# ArduinoV01.net
KiCad netlist of a schematic drawn in EAGLE
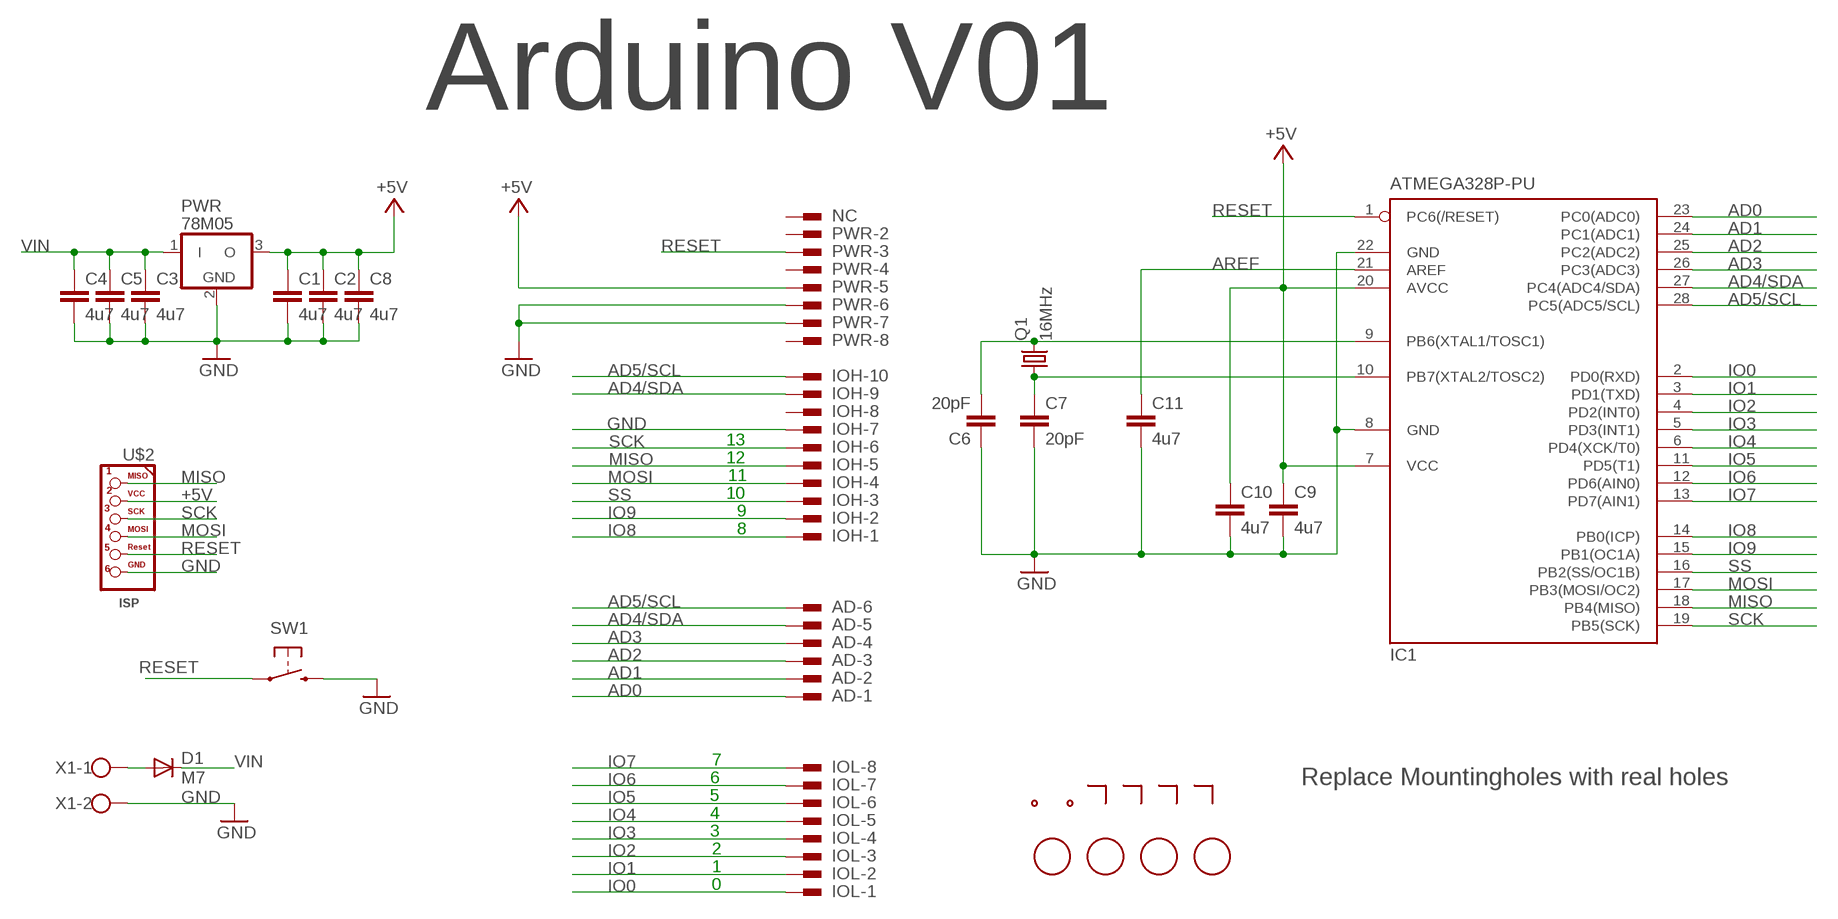
[diagram p0: schematic, sheet 1]

(export (version "E")
  (design (tool "Eeschema 10.0.6"))
  (components
    (comp (ref "AD-1")
      (value "PINHD-1X1")
      (footprint "eagle-import:1X01")
      (fields (field (name "MF") "TYCO ELECTRONICS") (field (name "MPN") "62221-1"))
      (libsource (lib "eagle-import") (part "PINHD-1X1"))
    )
    (comp (ref "AD-2")
      (value "PINHD-1X1")
      (footprint "eagle-import:1X01")
      (fields (field (name "MF") "TYCO ELECTRONICS") (field (name "MPN") "62221-1"))
      (libsource (lib "eagle-import") (part "PINHD-1X1"))
    )
    (comp (ref "AD-3")
      (value "PINHD-1X1")
      (footprint "eagle-import:1X01")
      (fields (field (name "MF") "TYCO ELECTRONICS") (field (name "MPN") "62221-1"))
      (libsource (lib "eagle-import") (part "PINHD-1X1"))
    )
    (comp (ref "AD-4")
      (value "PINHD-1X1")
      (footprint "eagle-import:1X01")
      (fields (field (name "MF") "TYCO ELECTRONICS") (field (name "MPN") "62221-1"))
      (libsource (lib "eagle-import") (part "PINHD-1X1"))
    )
    (comp (ref "AD-5")
      (value "PINHD-1X1")
      (footprint "eagle-import:1X01")
      (fields (field (name "MF") "TYCO ELECTRONICS") (field (name "MPN") "62221-1"))
      (libsource (lib "eagle-import") (part "PINHD-1X1"))
    )
    (comp (ref "AD-6")
      (value "PINHD-1X1")
      (footprint "eagle-import:1X01")
      (fields (field (name "MF") "TYCO ELECTRONICS") (field (name "MPN") "62221-1"))
      (libsource (lib "eagle-import") (part "PINHD-1X1"))
    )
    (comp (ref "C1")
      (value "4u7")
      (footprint "eagle-import:C0805")
      (libsource (lib "eagle-import") (part "C-EUC0805"))
    )
    (comp (ref "C2")
      (value "4u7")
      (footprint "eagle-import:C0805")
      (libsource (lib "eagle-import") (part "C-EUC0805"))
    )
    (comp (ref "C3")
      (value "4u7")
      (footprint "eagle-import:C0805")
      (libsource (lib "eagle-import") (part "C-EUC0805"))
    )
    (comp (ref "C4")
      (value "4u7")
      (footprint "eagle-import:C0805")
      (libsource (lib "eagle-import") (part "C-EUC0805"))
    )
    (comp (ref "C5")
      (value "4u7")
      (footprint "eagle-import:C0805")
      (libsource (lib "eagle-import") (part "C-EUC0805"))
    )
    (comp (ref "C6")
      (value "20pF")
      (footprint "eagle-import:C0805")
      (libsource (lib "eagle-import") (part "C-EUC0805"))
    )
    (comp (ref "C7")
      (value "20pF")
      (footprint "eagle-import:C0805")
      (libsource (lib "eagle-import") (part "C-EUC0805"))
    )
    (comp (ref "C8")
      (value "4u7")
      (footprint "eagle-import:C0805")
      (libsource (lib "eagle-import") (part "C-EUC0805"))
    )
    (comp (ref "C9")
      (value "4u7")
      (footprint "eagle-import:C0805")
      (libsource (lib "eagle-import") (part "C-EUC0805"))
    )
    (comp (ref "C10")
      (value "4u7")
      (footprint "eagle-import:C0805")
      (libsource (lib "eagle-import") (part "C-EUC0805"))
    )
    (comp (ref "C11")
      (value "4u7")
      (footprint "eagle-import:C0805")
      (libsource (lib "eagle-import") (part "C-EUC0805"))
    )
    (comp (ref "D1")
      (value "M7")
      (footprint "eagle-import:DO214AC")
      (libsource (lib "eagle-import") (part "DIODE-DO214AC"))
    )
    (comp (ref "FD1")
      (value "FIDUCIALMOUNT")
      (footprint "eagle-import:FIDUCIA-MOUNT")
      (libsource (lib "eagle-import") (part "FIDUCIALMOUNT"))
    )
    (comp (ref "FD2")
      (value "FIDUCIALMOUNT")
      (footprint "eagle-import:FIDUCIA-MOUNT")
      (libsource (lib "eagle-import") (part "FIDUCIALMOUNT"))
    )
    (comp (ref "FD3")
      (value "FIDUCIALMOUNT")
      (footprint "eagle-import:FIDUCIA-MOUNT")
      (libsource (lib "eagle-import") (part "FIDUCIALMOUNT"))
    )
    (comp (ref "FD4")
      (value "FIDUCIALMOUNT")
      (footprint "eagle-import:FIDUCIA-MOUNT")
      (libsource (lib "eagle-import") (part "FIDUCIALMOUNT"))
    )
    (comp (ref "IC1")
      (value "ATMEGA328P-PU")
      (footprint "eagle-import:DIL28-3")
      (libsource (lib "eagle-import") (part "ATMEGA328P-PU"))
    )
    (comp (ref "IOH-1")
      (value "PINHD-1X1")
      (footprint "eagle-import:1X01")
      (fields (field (name "MF") "TYCO ELECTRONICS") (field (name "MPN") "62221-1"))
      (libsource (lib "eagle-import") (part "PINHD-1X1"))
    )
    (comp (ref "IOH-2")
      (value "PINHD-1X1")
      (footprint "eagle-import:1X01")
      (fields (field (name "MF") "TYCO ELECTRONICS") (field (name "MPN") "62221-1"))
      (libsource (lib "eagle-import") (part "PINHD-1X1"))
    )
    (comp (ref "IOH-3")
      (value "PINHD-1X1")
      (footprint "eagle-import:1X01")
      (fields (field (name "MF") "TYCO ELECTRONICS") (field (name "MPN") "62221-1"))
      (libsource (lib "eagle-import") (part "PINHD-1X1"))
    )
    (comp (ref "IOH-4")
      (value "PINHD-1X1")
      (footprint "eagle-import:1X01")
      (fields (field (name "MF") "TYCO ELECTRONICS") (field (name "MPN") "62221-1"))
      (libsource (lib "eagle-import") (part "PINHD-1X1"))
    )
    (comp (ref "IOH-5")
      (value "PINHD-1X1")
      (footprint "eagle-import:1X01")
      (fields (field (name "MF") "TYCO ELECTRONICS") (field (name "MPN") "62221-1"))
      (libsource (lib "eagle-import") (part "PINHD-1X1"))
    )
    (comp (ref "IOH-6")
      (value "PINHD-1X1")
      (footprint "eagle-import:1X01")
      (fields (field (name "MF") "TYCO ELECTRONICS") (field (name "MPN") "62221-1"))
      (libsource (lib "eagle-import") (part "PINHD-1X1"))
    )
    (comp (ref "IOH-7")
      (value "PINHD-1X1")
      (footprint "eagle-import:1X01")
      (fields (field (name "MF") "TYCO ELECTRONICS") (field (name "MPN") "62221-1"))
      (libsource (lib "eagle-import") (part "PINHD-1X1"))
    )
    (comp (ref "IOH-8")
      (value "PINHD-1X1")
      (footprint "eagle-import:1X01")
      (fields (field (name "MF") "TYCO ELECTRONICS") (field (name "MPN") "62221-1"))
      (libsource (lib "eagle-import") (part "PINHD-1X1"))
    )
    (comp (ref "IOH-9")
      (value "PINHD-1X1")
      (footprint "eagle-import:1X01")
      (fields (field (name "MF") "TYCO ELECTRONICS") (field (name "MPN") "62221-1"))
      (libsource (lib "eagle-import") (part "PINHD-1X1"))
    )
    (comp (ref "IOH-10")
      (value "PINHD-1X1")
      (footprint "eagle-import:1X01")
      (fields (field (name "MF") "TYCO ELECTRONICS") (field (name "MPN") "62221-1"))
      (libsource (lib "eagle-import") (part "PINHD-1X1"))
    )
    (comp (ref "IOL-1")
      (value "PINHD-1X1")
      (footprint "eagle-import:1X01")
      (fields (field (name "MF") "TYCO ELECTRONICS") (field (name "MPN") "62221-1"))
      (libsource (lib "eagle-import") (part "PINHD-1X1"))
    )
    (comp (ref "IOL-2")
      (value "PINHD-1X1")
      (footprint "eagle-import:1X01")
      (fields (field (name "MF") "TYCO ELECTRONICS") (field (name "MPN") "62221-1"))
      (libsource (lib "eagle-import") (part "PINHD-1X1"))
    )
    (comp (ref "IOL-3")
      (value "PINHD-1X1")
      (footprint "eagle-import:1X01")
      (fields (field (name "MF") "TYCO ELECTRONICS") (field (name "MPN") "62221-1"))
      (libsource (lib "eagle-import") (part "PINHD-1X1"))
    )
    (comp (ref "IOL-4")
      (value "PINHD-1X1")
      (footprint "eagle-import:1X01")
      (fields (field (name "MF") "TYCO ELECTRONICS") (field (name "MPN") "62221-1"))
      (libsource (lib "eagle-import") (part "PINHD-1X1"))
    )
    (comp (ref "IOL-5")
      (value "PINHD-1X1")
      (footprint "eagle-import:1X01")
      (fields (field (name "MF") "TYCO ELECTRONICS") (field (name "MPN") "62221-1"))
      (libsource (lib "eagle-import") (part "PINHD-1X1"))
    )
    (comp (ref "IOL-6")
      (value "PINHD-1X1")
      (footprint "eagle-import:1X01")
      (fields (field (name "MF") "TYCO ELECTRONICS") (field (name "MPN") "62221-1"))
      (libsource (lib "eagle-import") (part "PINHD-1X1"))
    )
    (comp (ref "IOL-7")
      (value "PINHD-1X1")
      (footprint "eagle-import:1X01")
      (fields (field (name "MF") "TYCO ELECTRONICS") (field (name "MPN") "62221-1"))
      (libsource (lib "eagle-import") (part "PINHD-1X1"))
    )
    (comp (ref "IOL-8")
      (value "PINHD-1X1")
      (footprint "eagle-import:1X01")
      (fields (field (name "MF") "TYCO ELECTRONICS") (field (name "MPN") "62221-1"))
      (libsource (lib "eagle-import") (part "PINHD-1X1"))
    )
    (comp (ref "NC")
      (value "PINHD-1X1")
      (footprint "eagle-import:1X01")
      (fields (field (name "MF") "TYCO ELECTRONICS") (field (name "MPN") "62221-1"))
      (libsource (lib "eagle-import") (part "PINHD-1X1"))
    )
    (comp (ref "PWR")
      (value "78M05")
      (footprint "eagle-import:DPACK")
      (libsource (lib "eagle-import") (part "7805DPACK"))
    )
    (comp (ref "PWR-2")
      (value "PINHD-1X1")
      (footprint "eagle-import:1X01")
      (fields (field (name "MF") "TYCO ELECTRONICS") (field (name "MPN") "62221-1"))
      (libsource (lib "eagle-import") (part "PINHD-1X1"))
    )
    (comp (ref "PWR-3")
      (value "PINHD-1X1")
      (footprint "eagle-import:1X01")
      (fields (field (name "MF") "TYCO ELECTRONICS") (field (name "MPN") "62221-1"))
      (libsource (lib "eagle-import") (part "PINHD-1X1"))
    )
    (comp (ref "PWR-4")
      (value "PINHD-1X1")
      (footprint "eagle-import:1X01")
      (fields (field (name "MF") "TYCO ELECTRONICS") (field (name "MPN") "62221-1"))
      (libsource (lib "eagle-import") (part "PINHD-1X1"))
    )
    (comp (ref "PWR-5")
      (value "PINHD-1X1")
      (footprint "eagle-import:1X01")
      (fields (field (name "MF") "TYCO ELECTRONICS") (field (name "MPN") "62221-1"))
      (libsource (lib "eagle-import") (part "PINHD-1X1"))
    )
    (comp (ref "PWR-6")
      (value "PINHD-1X1")
      (footprint "eagle-import:1X01")
      (fields (field (name "MF") "TYCO ELECTRONICS") (field (name "MPN") "62221-1"))
      (libsource (lib "eagle-import") (part "PINHD-1X1"))
    )
    (comp (ref "PWR-7")
      (value "PINHD-1X1")
      (footprint "eagle-import:1X01")
      (fields (field (name "MF") "TYCO ELECTRONICS") (field (name "MPN") "62221-1"))
      (libsource (lib "eagle-import") (part "PINHD-1X1"))
    )
    (comp (ref "PWR-8")
      (value "PINHD-1X1")
      (footprint "eagle-import:1X01")
      (fields (field (name "MF") "TYCO ELECTRONICS") (field (name "MPN") "62221-1"))
      (libsource (lib "eagle-import") (part "PINHD-1X1"))
    )
    (comp (ref "Q1")
      (value "16MHz")
      (footprint "eagle-import:HC49_S")
      (libsource (lib "eagle-import") (part "CRYSTALHC49S"))
    )
    (comp (ref "SW1")
      (value "SWITCH1X2")
      (footprint "eagle-import:SW8X4-SMD")
      (libsource (lib "eagle-import") (part "SWITCH1X2"))
    )
    (comp (ref "U$1")
      (value "MARKERDUAL-90")
      (footprint "eagle-import:MARKER90")
      (libsource (lib "eagle-import") (part "MARKERDUAL-90"))
    )
    (comp (ref "U$2")
      (value "ISPE")
      (footprint "eagle-import:2X03EDGE")
      (libsource (lib "eagle-import") (part "ISPE"))
    )
    (comp (ref "U$3")
      (value "MARKER")
      (footprint "eagle-import:MARKER")
      (libsource (lib "eagle-import") (part "MARKER"))
    )
    (comp (ref "U$4")
      (value "MARKER")
      (footprint "eagle-import:MARKER")
      (libsource (lib "eagle-import") (part "MARKER"))
    )
    (comp (ref "U$5")
      (value "MARKER")
      (footprint "eagle-import:MARKER")
      (libsource (lib "eagle-import") (part "MARKER"))
    )
    (comp (ref "U$6")
      (value "MARKER")
      (footprint "eagle-import:MARKER")
      (libsource (lib "eagle-import") (part "MARKER"))
    )
    (comp (ref "X1")
      (value "SCREWTERMINATOR1X2V")
      (footprint "eagle-import:W237-102V")
      (libsource (lib "eagle-import") (part "SCREWTERMINATOR1X2V"))
    )
  )
  (nets
    (net (code "1") (name "+5V") (class "Default")
      (node (ref "C1") (pin "1") (pinfunction "1_1") (pintype "passive"))
      (node (ref "C10") (pin "1") (pinfunction "1_1") (pintype "passive"))
      (node (ref "C2") (pin "1") (pinfunction "1_1") (pintype "passive"))
      (node (ref "C8") (pin "1") (pinfunction "1_1") (pintype "passive"))
      (node (ref "C9") (pin "1") (pinfunction "1_1") (pintype "passive"))
      (node (ref "IC1") (pin "20") (pinfunction "AVCC_20") (pintype "power_in"))
      (node (ref "IC1") (pin "7") (pinfunction "VCC_7") (pintype "power_in"))
      (node (ref "PWR") (pin "3") (pinfunction "O_3") (pintype "passive"))
      (node (ref "PWR-5") (pin "1") (pinfunction "1_1") (pintype "passive"))
      (node (ref "U$2") (pin "P$2") (pinfunction "2_P$2") (pintype "passive"))
    )
    (net (code "2") (name "/AD0") (class "Default")
      (node (ref "AD-1") (pin "1") (pinfunction "1_1") (pintype "passive"))
      (node (ref "IC1") (pin "23") (pinfunction "PC0(ADC0)_23") (pintype "bidirectional"))
    )
    (net (code "3") (name "/AD1") (class "Default")
      (node (ref "AD-2") (pin "1") (pinfunction "1_1") (pintype "passive"))
      (node (ref "IC1") (pin "24") (pinfunction "PC1(ADC1)_24") (pintype "bidirectional"))
    )
    (net (code "4") (name "/AD2") (class "Default")
      (node (ref "AD-3") (pin "1") (pinfunction "1_1") (pintype "passive"))
      (node (ref "IC1") (pin "25") (pinfunction "PC2(ADC2)_25") (pintype "bidirectional"))
    )
    (net (code "5") (name "/AD3") (class "Default")
      (node (ref "AD-4") (pin "1") (pinfunction "1_1") (pintype "passive"))
      (node (ref "IC1") (pin "26") (pinfunction "PC3(ADC3)_26") (pintype "bidirectional"))
    )
    (net (code "6") (name "/AD4{slash}SDA") (class "Default")
      (node (ref "AD-5") (pin "1") (pinfunction "1_1") (pintype "passive"))
      (node (ref "IC1") (pin "27") (pinfunction "PC4(ADC4/SDA)_27") (pintype "bidirectional"))
      (node (ref "IOH-9") (pin "1") (pinfunction "1_1") (pintype "passive"))
    )
    (net (code "7") (name "/AD5{slash}SCL") (class "Default")
      (node (ref "AD-6") (pin "1") (pinfunction "1_1") (pintype "passive"))
      (node (ref "IC1") (pin "28") (pinfunction "PC5(ADC5/SCL)_28") (pintype "bidirectional"))
      (node (ref "IOH-10") (pin "1") (pinfunction "1_1") (pintype "passive"))
    )
    (net (code "8") (name "/AREF") (class "Default")
      (node (ref "C11") (pin "1") (pinfunction "1_1") (pintype "passive"))
      (node (ref "IC1") (pin "21") (pinfunction "AREF_21") (pintype "passive"))
    )
    (net (code "9") (name "/IO0") (class "Default")
      (node (ref "IC1") (pin "2") (pinfunction "PD0(RXD)_2") (pintype "bidirectional"))
      (node (ref "IOL-1") (pin "1") (pinfunction "1_1") (pintype "passive"))
    )
    (net (code "10") (name "/IO1") (class "Default")
      (node (ref "IC1") (pin "3") (pinfunction "PD1(TXD)_3") (pintype "bidirectional"))
      (node (ref "IOL-2") (pin "1") (pinfunction "1_1") (pintype "passive"))
    )
    (net (code "11") (name "/IO2") (class "Default")
      (node (ref "IC1") (pin "4") (pinfunction "PD2(INT0)_4") (pintype "bidirectional"))
      (node (ref "IOL-3") (pin "1") (pinfunction "1_1") (pintype "passive"))
    )
    (net (code "12") (name "/IO3") (class "Default")
      (node (ref "IC1") (pin "5") (pinfunction "PD3(INT1)_5") (pintype "bidirectional"))
      (node (ref "IOL-4") (pin "1") (pinfunction "1_1") (pintype "passive"))
    )
    (net (code "13") (name "/IO4") (class "Default")
      (node (ref "IC1") (pin "6") (pinfunction "PD4(XCK/T0)_6") (pintype "bidirectional"))
      (node (ref "IOL-5") (pin "1") (pinfunction "1_1") (pintype "passive"))
    )
    (net (code "14") (name "/IO5") (class "Default")
      (node (ref "IC1") (pin "11") (pinfunction "PD5(T1)_11") (pintype "bidirectional"))
      (node (ref "IOL-6") (pin "1") (pinfunction "1_1") (pintype "passive"))
    )
    (net (code "15") (name "/IO6") (class "Default")
      (node (ref "IC1") (pin "12") (pinfunction "PD6(AIN0)_12") (pintype "bidirectional"))
      (node (ref "IOL-7") (pin "1") (pinfunction "1_1") (pintype "passive"))
    )
    (net (code "16") (name "/IO7") (class "Default")
      (node (ref "IC1") (pin "13") (pinfunction "PD7(AIN1)_13") (pintype "bidirectional"))
      (node (ref "IOL-8") (pin "1") (pinfunction "1_1") (pintype "passive"))
    )
    (net (code "17") (name "/IO8") (class "Default")
      (node (ref "IC1") (pin "14") (pinfunction "PB0(ICP)_14") (pintype "bidirectional"))
      (node (ref "IOH-1") (pin "1") (pinfunction "1_1") (pintype "passive"))
    )
    (net (code "18") (name "/IO9") (class "Default")
      (node (ref "IC1") (pin "15") (pinfunction "PB1(OC1A)_15") (pintype "bidirectional"))
      (node (ref "IOH-2") (pin "1") (pinfunction "1_1") (pintype "passive"))
    )
    (net (code "19") (name "/MISO") (class "Default")
      (node (ref "IC1") (pin "18") (pinfunction "PB4(MISO)_18") (pintype "bidirectional"))
      (node (ref "IOH-5") (pin "1") (pinfunction "1_1") (pintype "passive"))
      (node (ref "U$2") (pin "P$1") (pinfunction "1_P$1") (pintype "passive"))
    )
    (net (code "20") (name "/MOSI") (class "Default")
      (node (ref "IC1") (pin "17") (pinfunction "PB3(MOSI/OC2)_17") (pintype "bidirectional"))
      (node (ref "IOH-4") (pin "1") (pinfunction "1_1") (pintype "passive"))
      (node (ref "U$2") (pin "P$4") (pinfunction "4_P$4") (pintype "passive"))
    )
    (net (code "21") (name "/RESET") (class "Default")
      (node (ref "IC1") (pin "1") (pinfunction "PC6(/RESET)_1") (pintype "bidirectional"))
      (node (ref "PWR-3") (pin "1") (pinfunction "1_1") (pintype "passive"))
      (node (ref "SW1") (pin "1") (pinfunction "P_1") (pintype "passive"))
      (node (ref "U$2") (pin "P$5") (pinfunction "5_P$5") (pintype "passive"))
    )
    (net (code "22") (name "/SCK") (class "Default")
      (node (ref "IC1") (pin "19") (pinfunction "PB5(SCK)_19") (pintype "bidirectional"))
      (node (ref "IOH-6") (pin "1") (pinfunction "1_1") (pintype "passive"))
      (node (ref "U$2") (pin "P$3") (pinfunction "3_P$3") (pintype "passive"))
    )
    (net (code "23") (name "/SS") (class "Default")
      (node (ref "IC1") (pin "16") (pinfunction "PB2(SS/OC1B)_16") (pintype "bidirectional"))
      (node (ref "IOH-3") (pin "1") (pinfunction "1_1") (pintype "passive"))
    )
    (net (code "24") (name "/VIN") (class "Default")
      (node (ref "C3") (pin "1") (pinfunction "1_1") (pintype "passive"))
      (node (ref "C4") (pin "1") (pinfunction "1_1") (pintype "passive"))
      (node (ref "C5") (pin "1") (pinfunction "1_1") (pintype "passive"))
      (node (ref "D1") (pin "C") (pinfunction "C_C") (pintype "passive"))
      (node (ref "PWR") (pin "1") (pinfunction "I_1") (pintype "input"))
    )
    (net (code "25") (name "GND") (class "Default")
      (node (ref "C1") (pin "2") (pinfunction "2_2") (pintype "passive"))
      (node (ref "C10") (pin "2") (pinfunction "2_2") (pintype "passive"))
      (node (ref "C11") (pin "2") (pinfunction "2_2") (pintype "passive"))
      (node (ref "C2") (pin "2") (pinfunction "2_2") (pintype "passive"))
      (node (ref "C3") (pin "2") (pinfunction "2_2") (pintype "passive"))
      (node (ref "C4") (pin "2") (pinfunction "2_2") (pintype "passive"))
      (node (ref "C5") (pin "2") (pinfunction "2_2") (pintype "passive"))
      (node (ref "C6") (pin "1") (pinfunction "1_1") (pintype "passive"))
      (node (ref "C7") (pin "2") (pinfunction "2_2") (pintype "passive"))
      (node (ref "C8") (pin "2") (pinfunction "2_2") (pintype "passive"))
      (node (ref "C9") (pin "2") (pinfunction "2_2") (pintype "passive"))
      (node (ref "IC1") (pin "22") (pinfunction "GND_22") (pintype "power_in"))
      (node (ref "IC1") (pin "8") (pinfunction "GND_8") (pintype "power_in"))
      (node (ref "IOH-7") (pin "1") (pinfunction "1_1") (pintype "passive"))
      (node (ref "PWR") (pin "2") (pinfunction "GND_2") (pintype "passive"))
      (node (ref "PWR-6") (pin "1") (pinfunction "1_1") (pintype "passive"))
      (node (ref "PWR-7") (pin "1") (pinfunction "1_1") (pintype "passive"))
      (node (ref "SW1") (pin "2") (pinfunction "S_2") (pintype "passive"))
      (node (ref "U$2") (pin "P$6") (pinfunction "6_P$6") (pintype "passive"))
      (node (ref "X1") (pin "2") (pinfunction "KL_2") (pintype "passive"))
    )
    (net (code "26") (name "Net-(IC1-PB6(XTAL1{slash}TOSC1))") (class "Default")
      (node (ref "C6") (pin "2") (pinfunction "2_2") (pintype "passive"))
      (node (ref "IC1") (pin "9") (pinfunction "PB6(XTAL1/TOSC1)_9") (pintype "bidirectional"))
      (node (ref "Q1") (pin "2") (pinfunction "2_2") (pintype "passive"))
    )
    (net (code "27") (name "Net-(IC1-PB7(XTAL2{slash}TOSC2))") (class "Default")
      (node (ref "C7") (pin "1") (pinfunction "1_1") (pintype "passive"))
      (node (ref "IC1") (pin "10") (pinfunction "PB7(XTAL2/TOSC2)_10") (pintype "bidirectional"))
      (node (ref "Q1") (pin "1") (pinfunction "1_1") (pintype "passive"))
    )
    (net (code "28") (name "Net-(X1A-KL)") (class "Default")
      (node (ref "D1") (pin "A") (pinfunction "A_A") (pintype "passive"))
      (node (ref "X1") (pin "1") (pinfunction "KL_1") (pintype "passive"))
    )
    (net (code "29") (name "unconnected-(IOH-8-Pad1)") (class "Default")
      (node (ref "IOH-8") (pin "1") (pinfunction "1_1") (pintype "passive"))
    )
    (net (code "30") (name "unconnected-(NC-Pad1)") (class "Default")
      (node (ref "NC") (pin "1") (pinfunction "1_1") (pintype "passive"))
    )
    (net (code "31") (name "unconnected-(PWR-2-Pad1)") (class "Default")
      (node (ref "PWR-2") (pin "1") (pinfunction "1_1") (pintype "passive"))
    )
    (net (code "32") (name "unconnected-(PWR-4-Pad1)") (class "Default")
      (node (ref "PWR-4") (pin "1") (pinfunction "1_1") (pintype "passive"))
    )
    (net (code "33") (name "unconnected-(PWR-8-Pad1)") (class "Default")
      (node (ref "PWR-8") (pin "1") (pinfunction "1_1") (pintype "passive"))
    )
  )
)
